# task8.net
KiCad netlist of a schematic drawn in EAGLE
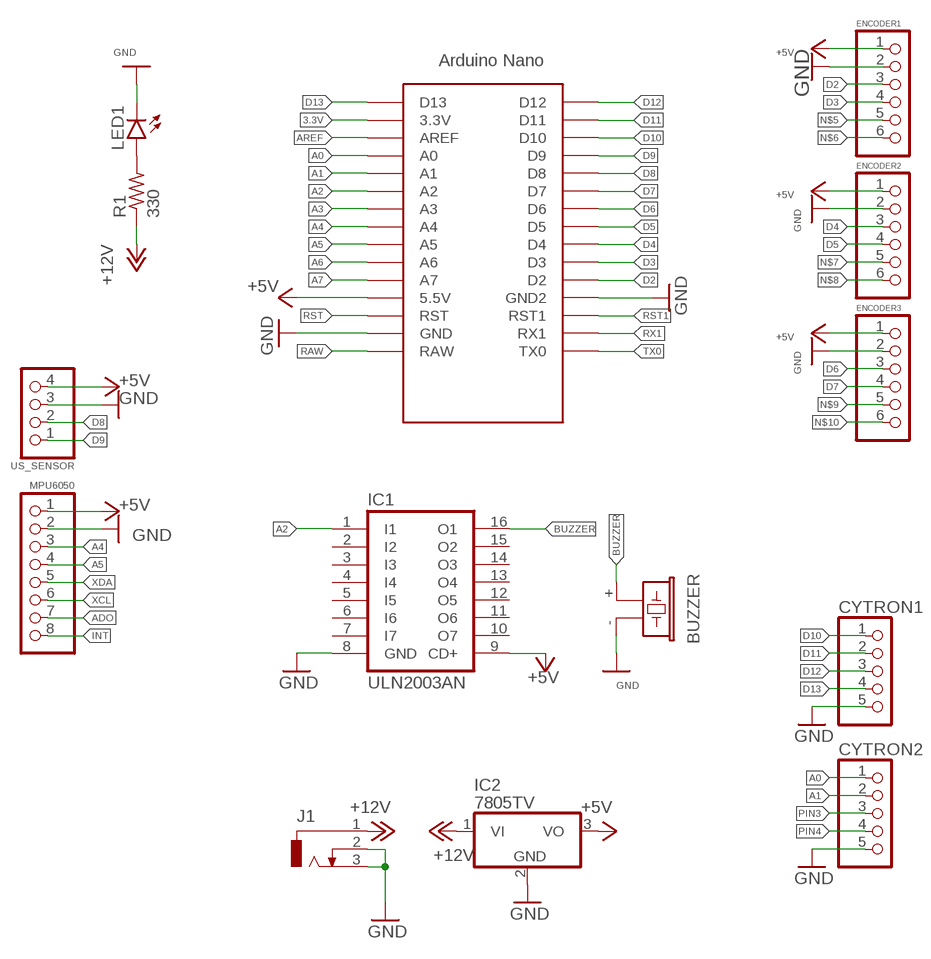
[diagram p0: schematic, sheet 1]

(export (version "E")
  (design (tool "Eeschema 10.0.6"))
  (components
    (comp (ref "CYTRON1")
      (value "PINHD-1X5")
      (footprint "eagle-import:1X05")
      (libsource (lib "eagle-import") (part "PINHD-1X5"))
    )
    (comp (ref "CYTRON2")
      (value "PINHD-1X5")
      (footprint "eagle-import:1X05")
      (libsource (lib "eagle-import") (part "PINHD-1X5"))
    )
    (comp (ref "ENCODER1")
      (value "PINHD-1X6")
      (footprint "eagle-import:1X06")
      (libsource (lib "eagle-import") (part "PINHD-1X6"))
    )
    (comp (ref "ENCODER2")
      (value "PINHD-1X6")
      (footprint "eagle-import:1X06")
      (libsource (lib "eagle-import") (part "PINHD-1X6"))
    )
    (comp (ref "ENCODER3")
      (value "PINHD-1X6")
      (footprint "eagle-import:1X06")
      (libsource (lib "eagle-import") (part "PINHD-1X6"))
    )
    (comp (ref "IC1")
      (value "ULN2003AN")
      (footprint "eagle-import:DIL16")
      (libsource (lib "eagle-import") (part "ULN2003AN"))
    )
    (comp (ref "IC2")
      (value "7805TV")
      (footprint "eagle-import:TO220V")
      (libsource (lib "eagle-import") (part "78TV05"))
    )
    (comp (ref "J1")
      (value "CON_JACK")
      (footprint "eagle-import:DCJ0303")
      (libsource (lib "eagle-import") (part "CON_JACK"))
    )
    (comp (ref "LED1")
      (value "LED5MM")
      (footprint "eagle-import:LED5MM")
      (libsource (lib "eagle-import") (part "LED5MM"))
    )
    (comp (ref "MPU6050")
      (value "PINHD-1X8")
      (footprint "eagle-import:1X08")
      (libsource (lib "eagle-import") (part "PINHD-1X8"))
    )
    (comp (ref "R1")
      (value "330")
      (footprint "eagle-import:0204_7")
      (fields (field (name "POPULARITY") "330"))
      (libsource (lib "eagle-import") (part "R-US_0204/7"))
    )
    (comp (ref "SG1")
      (value "BUZZER")
      (footprint "eagle-import:F_CM12P")
      (libsource (lib "eagle-import") (part "BUZZER"))
    )
    (comp (ref "U$1")
      (value "ARDUINO_NANO")
      (footprint "eagle-import:NANO")
      (libsource (lib "eagle-import") (part "ARDUINO_NANO"))
    )
    (comp (ref "US_SENSOR")
      (value "PINHD-1X4")
      (footprint "eagle-import:1X04")
      (libsource (lib "eagle-import") (part "PINHD-1X4"))
    )
  )
  (nets
    (net (code "1") (name "+5V") (class "Default")
      (node (ref "ENCODER1") (pin "1") (pinfunction "1_1") (pintype "passive"))
      (node (ref "ENCODER2") (pin "1") (pinfunction "1_1") (pintype "passive"))
      (node (ref "ENCODER3") (pin "1") (pinfunction "1_1") (pintype "passive"))
      (node (ref "IC1") (pin "9") (pinfunction "CD+_9") (pintype "passive"))
      (node (ref "IC2") (pin "3") (pinfunction "VO_3") (pintype "passive"))
      (node (ref "MPU6050") (pin "1") (pinfunction "1_1") (pintype "passive"))
      (node (ref "U$1") (pin "5V") (pinfunction "5.5V_5V") (pintype "bidirectional"))
      (node (ref "US_SENSOR") (pin "4") (pinfunction "4_4") (pintype "passive"))
    )
    (net (code "2") (name "+12V") (class "Default")
      (node (ref "IC2") (pin "1") (pinfunction "VI_1") (pintype "input"))
      (node (ref "J1") (pin "1") (pinfunction "1_1") (pintype "passive"))
      (node (ref "R1") (pin "1") (pinfunction "1_1") (pintype "passive"))
    )
    (net (code "3") (name "3.3V") (class "Default")
      (node (ref "U$1") (pin "3.3V") (pinfunction "3.3V_3.3V") (pintype "bidirectional"))
    )
    (net (code "4") (name "A0") (class "Default")
      (node (ref "CYTRON2") (pin "1") (pinfunction "1_1") (pintype "passive"))
      (node (ref "U$1") (pin "A0") (pinfunction "A0_A0") (pintype "bidirectional"))
    )
    (net (code "5") (name "A1") (class "Default")
      (node (ref "CYTRON2") (pin "2") (pinfunction "2_2") (pintype "passive"))
      (node (ref "U$1") (pin "A1") (pinfunction "A1_A1") (pintype "bidirectional"))
    )
    (net (code "6") (name "A2") (class "Default")
      (node (ref "IC1") (pin "1") (pinfunction "I1_1") (pintype "input"))
      (node (ref "U$1") (pin "A2") (pinfunction "A2_A2") (pintype "bidirectional"))
    )
    (net (code "7") (name "A3") (class "Default")
      (node (ref "U$1") (pin "A3") (pinfunction "A3_A3") (pintype "bidirectional"))
    )
    (net (code "8") (name "A4") (class "Default")
      (node (ref "MPU6050") (pin "3") (pinfunction "3_3") (pintype "passive"))
      (node (ref "U$1") (pin "A4") (pinfunction "A4_A4") (pintype "bidirectional"))
    )
    (net (code "9") (name "A5") (class "Default")
      (node (ref "MPU6050") (pin "4") (pinfunction "4_4") (pintype "passive"))
      (node (ref "U$1") (pin "A5") (pinfunction "A5_A5") (pintype "bidirectional"))
    )
    (net (code "10") (name "A6") (class "Default")
      (node (ref "U$1") (pin "A6") (pinfunction "A6_A6") (pintype "bidirectional"))
    )
    (net (code "11") (name "A7") (class "Default")
      (node (ref "U$1") (pin "A7") (pinfunction "A7_A7") (pintype "bidirectional"))
    )
    (net (code "12") (name "ADO") (class "Default")
      (node (ref "MPU6050") (pin "7") (pinfunction "7_7") (pintype "passive"))
    )
    (net (code "13") (name "AREF") (class "Default")
      (node (ref "U$1") (pin "AREF") (pinfunction "AREF_AREF") (pintype "bidirectional"))
    )
    (net (code "14") (name "BUZZER") (class "Default")
      (node (ref "IC1") (pin "16") (pinfunction "O1_16") (pintype "open_collector"))
      (node (ref "SG1") (pin "+") (pinfunction "1_+") (pintype "passive"))
    )
    (net (code "15") (name "D2") (class "Default")
      (node (ref "ENCODER1") (pin "3") (pinfunction "3_3") (pintype "passive"))
      (node (ref "U$1") (pin "D2") (pinfunction "D2_D2") (pintype "bidirectional"))
    )
    (net (code "16") (name "D3") (class "Default")
      (node (ref "ENCODER1") (pin "4") (pinfunction "4_4") (pintype "passive"))
      (node (ref "U$1") (pin "D3") (pinfunction "D3_D3") (pintype "bidirectional"))
    )
    (net (code "17") (name "D4") (class "Default")
      (node (ref "ENCODER2") (pin "3") (pinfunction "3_3") (pintype "passive"))
      (node (ref "U$1") (pin "D4") (pinfunction "D4_D4") (pintype "bidirectional"))
    )
    (net (code "18") (name "D5") (class "Default")
      (node (ref "ENCODER2") (pin "4") (pinfunction "4_4") (pintype "passive"))
      (node (ref "U$1") (pin "D5") (pinfunction "D5_D5") (pintype "bidirectional"))
    )
    (net (code "19") (name "D6") (class "Default")
      (node (ref "ENCODER3") (pin "3") (pinfunction "3_3") (pintype "passive"))
      (node (ref "U$1") (pin "D6") (pinfunction "D6_D6") (pintype "bidirectional"))
    )
    (net (code "20") (name "D7") (class "Default")
      (node (ref "ENCODER3") (pin "4") (pinfunction "4_4") (pintype "passive"))
      (node (ref "U$1") (pin "D7") (pinfunction "D7_D7") (pintype "bidirectional"))
    )
    (net (code "21") (name "D8") (class "Default")
      (node (ref "U$1") (pin "D8") (pinfunction "D8_D8") (pintype "bidirectional"))
      (node (ref "US_SENSOR") (pin "2") (pinfunction "2_2") (pintype "passive"))
    )
    (net (code "22") (name "D9") (class "Default")
      (node (ref "U$1") (pin "D9") (pinfunction "D9_D9") (pintype "bidirectional"))
      (node (ref "US_SENSOR") (pin "1") (pinfunction "1_1") (pintype "passive"))
    )
    (net (code "23") (name "D10") (class "Default")
      (node (ref "CYTRON1") (pin "1") (pinfunction "1_1") (pintype "passive"))
      (node (ref "U$1") (pin "D10") (pinfunction "D10_D10") (pintype "bidirectional"))
    )
    (net (code "24") (name "D11") (class "Default")
      (node (ref "CYTRON1") (pin "2") (pinfunction "2_2") (pintype "passive"))
      (node (ref "U$1") (pin "D11") (pinfunction "D11_D11") (pintype "bidirectional"))
    )
    (net (code "25") (name "D12") (class "Default")
      (node (ref "CYTRON1") (pin "3") (pinfunction "3_3") (pintype "passive"))
      (node (ref "U$1") (pin "D12") (pinfunction "D12_D12") (pintype "bidirectional"))
    )
    (net (code "26") (name "D13") (class "Default")
      (node (ref "CYTRON1") (pin "4") (pinfunction "4_4") (pintype "passive"))
      (node (ref "U$1") (pin "D13") (pinfunction "D13_D13") (pintype "bidirectional"))
    )
    (net (code "27") (name "GND") (class "Default")
      (node (ref "CYTRON1") (pin "5") (pinfunction "5_5") (pintype "passive"))
      (node (ref "CYTRON2") (pin "5") (pinfunction "5_5") (pintype "passive"))
      (node (ref "ENCODER1") (pin "2") (pinfunction "2_2") (pintype "passive"))
      (node (ref "ENCODER2") (pin "2") (pinfunction "2_2") (pintype "passive"))
      (node (ref "ENCODER3") (pin "2") (pinfunction "2_2") (pintype "passive"))
      (node (ref "IC1") (pin "8") (pinfunction "GND_8") (pintype "power_in"))
      (node (ref "IC2") (pin "2") (pinfunction "GND_2") (pintype "passive"))
      (node (ref "J1") (pin "2") (pinfunction "2_2") (pintype "passive"))
      (node (ref "J1") (pin "3") (pinfunction "3_3") (pintype "passive"))
      (node (ref "LED1") (pin "K") (pinfunction "C_K") (pintype "passive"))
      (node (ref "MPU6050") (pin "2") (pinfunction "2_2") (pintype "passive"))
      (node (ref "SG1") (pin "-") (pinfunction "2_-") (pintype "passive"))
      (node (ref "U$1") (pin "GND") (pinfunction "GND_GND") (pintype "bidirectional"))
      (node (ref "U$1") (pin "GND1") (pinfunction "GND2_GND1") (pintype "bidirectional"))
      (node (ref "US_SENSOR") (pin "3") (pinfunction "3_3") (pintype "passive"))
    )
    (net (code "28") (name "INT") (class "Default")
      (node (ref "MPU6050") (pin "8") (pinfunction "8_8") (pintype "passive"))
    )
    (net (code "29") (name "N$5") (class "Default")
      (node (ref "ENCODER1") (pin "5") (pinfunction "5_5") (pintype "passive"))
    )
    (net (code "30") (name "N$6") (class "Default")
      (node (ref "ENCODER1") (pin "6") (pinfunction "6_6") (pintype "passive"))
    )
    (net (code "31") (name "N$7") (class "Default")
      (node (ref "ENCODER2") (pin "5") (pinfunction "5_5") (pintype "passive"))
    )
    (net (code "32") (name "N$8") (class "Default")
      (node (ref "ENCODER2") (pin "6") (pinfunction "6_6") (pintype "passive"))
    )
    (net (code "33") (name "N$9") (class "Default")
      (node (ref "ENCODER3") (pin "5") (pinfunction "5_5") (pintype "passive"))
    )
    (net (code "34") (name "N$10") (class "Default")
      (node (ref "ENCODER3") (pin "6") (pinfunction "6_6") (pintype "passive"))
    )
    (net (code "35") (name "Net-(LED1-PadA)") (class "Default")
      (node (ref "LED1") (pin "A") (pinfunction "A_A") (pintype "passive"))
      (node (ref "R1") (pin "2") (pinfunction "2_2") (pintype "passive"))
    )
    (net (code "36") (name "PIN3") (class "Default")
      (node (ref "CYTRON2") (pin "3") (pinfunction "3_3") (pintype "passive"))
    )
    (net (code "37") (name "PIN4") (class "Default")
      (node (ref "CYTRON2") (pin "4") (pinfunction "4_4") (pintype "passive"))
    )
    (net (code "38") (name "RAW") (class "Default")
      (node (ref "U$1") (pin "RAW") (pinfunction "RAW_RAW") (pintype "bidirectional"))
    )
    (net (code "39") (name "RST") (class "Default")
      (node (ref "U$1") (pin "RST") (pinfunction "RST_RST") (pintype "bidirectional"))
    )
    (net (code "40") (name "RST1") (class "Default")
      (node (ref "U$1") (pin "RST1") (pinfunction "RST1_RST1") (pintype "bidirectional"))
    )
    (net (code "41") (name "RX1") (class "Default")
      (node (ref "U$1") (pin "RX1") (pinfunction "RX1_RX1") (pintype "bidirectional"))
    )
    (net (code "42") (name "TX0") (class "Default")
      (node (ref "U$1") (pin "TX0") (pinfunction "TX0_TX0") (pintype "bidirectional"))
    )
    (net (code "43") (name "XCL") (class "Default")
      (node (ref "MPU6050") (pin "6") (pinfunction "6_6") (pintype "passive"))
    )
    (net (code "44") (name "XDA") (class "Default")
      (node (ref "MPU6050") (pin "5") (pinfunction "5_5") (pintype "passive"))
    )
    (net (code "45") (name "unconnected-(IC1-I2-Pad2)") (class "Default")
      (node (ref "IC1") (pin "2") (pinfunction "I2_2") (pintype "input"))
    )
    (net (code "46") (name "unconnected-(IC1-I3-Pad3)") (class "Default")
      (node (ref "IC1") (pin "3") (pinfunction "I3_3") (pintype "input"))
    )
    (net (code "47") (name "unconnected-(IC1-I4-Pad4)") (class "Default")
      (node (ref "IC1") (pin "4") (pinfunction "I4_4") (pintype "input"))
    )
    (net (code "48") (name "unconnected-(IC1-I5-Pad5)") (class "Default")
      (node (ref "IC1") (pin "5") (pinfunction "I5_5") (pintype "input"))
    )
    (net (code "49") (name "unconnected-(IC1-I6-Pad6)") (class "Default")
      (node (ref "IC1") (pin "6") (pinfunction "I6_6") (pintype "input"))
    )
    (net (code "50") (name "unconnected-(IC1-I7-Pad7)") (class "Default")
      (node (ref "IC1") (pin "7") (pinfunction "I7_7") (pintype "input"))
    )
    (net (code "51") (name "unconnected-(IC1-O2-Pad15)") (class "Default")
      (node (ref "IC1") (pin "15") (pinfunction "O2_15") (pintype "open_collector"))
    )
    (net (code "52") (name "unconnected-(IC1-O3-Pad14)") (class "Default")
      (node (ref "IC1") (pin "14") (pinfunction "O3_14") (pintype "open_collector"))
    )
    (net (code "53") (name "unconnected-(IC1-O4-Pad13)") (class "Default")
      (node (ref "IC1") (pin "13") (pinfunction "O4_13") (pintype "open_collector"))
    )
    (net (code "54") (name "unconnected-(IC1-O5-Pad12)") (class "Default")
      (node (ref "IC1") (pin "12") (pinfunction "O5_12") (pintype "open_collector"))
    )
    (net (code "55") (name "unconnected-(IC1-O6-Pad11)") (class "Default")
      (node (ref "IC1") (pin "11") (pinfunction "O6_11") (pintype "open_collector"))
    )
    (net (code "56") (name "unconnected-(IC1-O7-Pad10)") (class "Default")
      (node (ref "IC1") (pin "10") (pinfunction "O7_10") (pintype "open_collector"))
    )
  )
)
